# MCP_IO_expander.net
KiCad netlist of a schematic drawn in Altium Designer
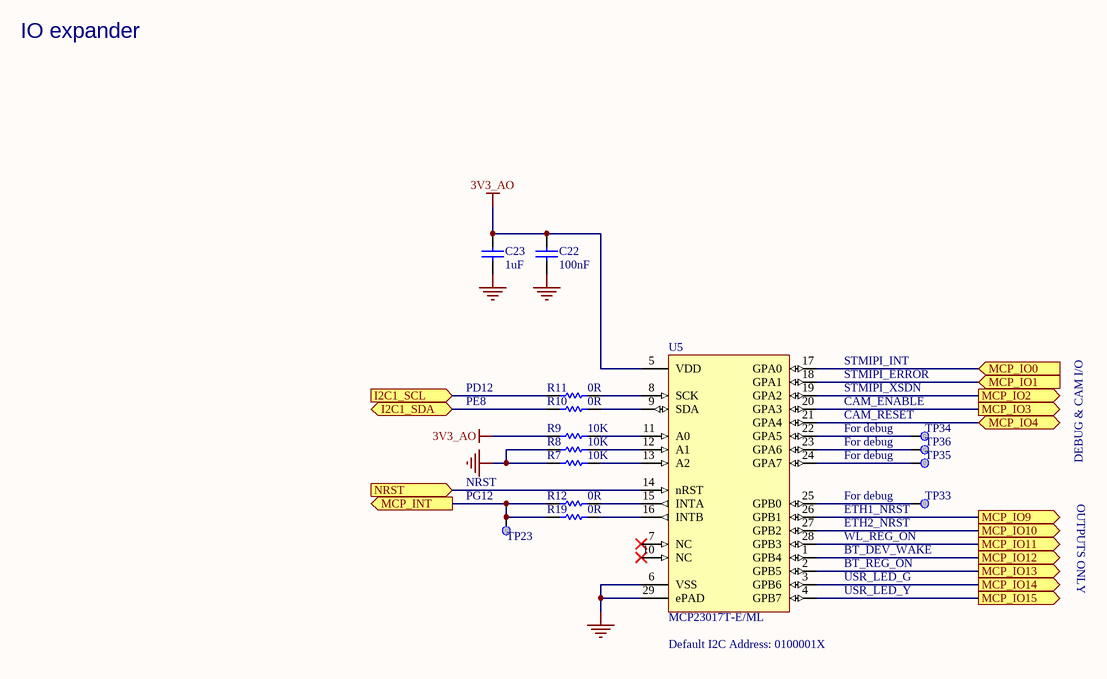
[diagram p0: MCP_IO_expander.SchDoc]

(export (version "E")
  (design (tool "Eeschema 10.0.6"))
  (components
    (comp (ref "C22")
      (value "100nF")
      (footprint "C0402")
      (description "Capacitor, MLCC, 100nF, 16V, X7R, +/-10%, 0402, T=0.5mm")
      (fields (field (name "INTERNAL_PART_NUMBER") "MCD-00006") (field (name "MANUFACTURER") "YAGEO"))
      (libsource (lib "MCD_PARTS_database") (part "Capacitor"))
    )
    (comp (ref "C23")
      (value "1uF")
      (footprint "C0201_MURATA_GRM033_H0P3")
      (description "Capacitor, MLCC, 1uF, 6.3V, X5R, +/-20%, 0201, T=0,3mm")
      (fields (field (name "INTERNAL_PART_NUMBER") "MCD-02377") (field (name "MANUFACTURER") "MURATA"))
      (libsource (lib "MCD_PARTS_database") (part "Capacitor"))
    )
    (comp (ref "R7")
      (value "10K")
      (footprint "R0402")
      (description "Resistor, 10K, 0402, +/-1%, 1/16W")
      (fields (field (name "INTERNAL_PART_NUMBER") "MCD-00053") (field (name "BMS_PART_NUMBER") "9131590"))
      (libsource (lib "MCD_PARTS_database") (part "Resistor"))
    )
    (comp (ref "R8")
      (value "10K")
      (footprint "R0402")
      (description "Resistor, 10K, 0402, +/-1%, 1/16W")
      (fields (field (name "INTERNAL_PART_NUMBER") "MCD-00053") (field (name "BMS_PART_NUMBER") "9131590"))
      (libsource (lib "MCD_PARTS_database") (part "Resistor"))
    )
    (comp (ref "R9")
      (value "10K")
      (footprint "R0402")
      (description "Resistor, 10K, 0402, +/-1%, 1/16W")
      (fields (field (name "INTERNAL_PART_NUMBER") "MCD-00053") (field (name "BMS_PART_NUMBER") "9131590"))
      (libsource (lib "MCD_PARTS_database") (part "Resistor"))
    )
    (comp (ref "R10")
      (value "0R")
      (footprint "R0402")
      (description "Resistor, 0R, 0402, +/-5%, 1/16W")
      (fields (field (name "INTERNAL_PART_NUMBER") "MCD-00052") (field (name "MANUFACTURER") "YAGEO"))
      (libsource (lib "MCD_PARTS_database") (part "Resistor"))
    )
    (comp (ref "R11")
      (value "0R")
      (footprint "R0402")
      (description "Resistor, 0R, 0402, +/-5%, 1/16W")
      (fields (field (name "INTERNAL_PART_NUMBER") "MCD-00052") (field (name "MANUFACTURER") "YAGEO"))
      (libsource (lib "MCD_PARTS_database") (part "Resistor"))
    )
    (comp (ref "R12")
      (value "0R")
      (footprint "R0402")
      (description "Resistor, 0R, 0402, +/-5%, 1/16W")
      (fields (field (name "INTERNAL_PART_NUMBER") "MCD-00052") (field (name "MANUFACTURER") "YAGEO"))
      (libsource (lib "MCD_PARTS_database") (part "Resistor"))
    )
    (comp (ref "R19")
      (value "0R")
      (footprint "R0402")
      (description "Resistor, 0R, 0402, +/-5%, 1/16W")
      (fields (field (name "INTERNAL_PART_NUMBER") "MCD-00052") (field (name "MANUFACTURER") "YAGEO"))
      (libsource (lib "MCD_PARTS_database") (part "Resistor"))
    )
    (comp (ref "TP23")
      (value "Test Point")
      (footprint "TP_SMD_1MM")
      (description "Test Point 1mm")
      (fields (field (name "INTERNAL_PART_NUMBER") "MCD-00074"))
      (libsource (lib "") (part "Test Point_1"))
    )
    (comp (ref "TP33")
      (value "Test Point")
      (footprint "TP_SMD_1MM")
      (description "Test Point 1mm")
      (fields (field (name "INTERNAL_PART_NUMBER") "MCD-00074"))
      (libsource (lib "MCD_PARTS_database") (part "Test Point"))
    )
    (comp (ref "TP34")
      (value "Test Point")
      (footprint "TP_SMD_1MM")
      (description "Test Point 1mm")
      (fields (field (name "INTERNAL_PART_NUMBER") "MCD-00074"))
      (libsource (lib "MCD_PARTS_database") (part "Test Point"))
    )
    (comp (ref "TP35")
      (value "Test Point")
      (footprint "TP_SMD_1MM")
      (description "Test Point 1mm")
      (fields (field (name "INTERNAL_PART_NUMBER") "MCD-00074"))
      (libsource (lib "MCD_PARTS_database") (part "Test Point"))
    )
    (comp (ref "TP36")
      (value "Test Point")
      (footprint "TP_SMD_1MM")
      (description "Test Point 1mm")
      (fields (field (name "INTERNAL_PART_NUMBER") "MCD-00074"))
      (libsource (lib "MCD_PARTS_database") (part "Test Point"))
    )
    (comp (ref "U5")
      (value "MCP23017T-E/ML")
      (footprint "ICC_QFN28-EPAD_6X6_P065")
      (description "16-bit port expander with I2C control")
      (fields (field (name "INTERNAL_PART_NUMBER") "MCD-02210") (field (name "MANUFACTURER") "MICROCHIP"))
      (libsource (lib "MCD_PARTS_database") (part "MCP23017"))
    )
  )
  (nets
    (net (code "1") (name "/I2C1_SCL") (class "Default")
      (node (ref "R11") (pin "1") (pinfunction "1_1") (pintype "passive"))
    )
    (net (code "2") (name "/I2C1_SDA") (class "Default")
      (node (ref "R10") (pin "1") (pinfunction "1_1") (pintype "passive"))
    )
    (net (code "3") (name "/MCP_INT") (class "Default")
      (node (ref "R12") (pin "1") (pinfunction "1_1") (pintype "passive"))
      (node (ref "R19") (pin "1") (pinfunction "1_1") (pintype "passive"))
      (node (ref "TP23") (pin "1") (pinfunction "1_1") (pintype "passive"))
    )
    (net (code "4") (name "/MCP_IO0") (class "Default")
      (node (ref "U5") (pin "17") (pinfunction "GPA0_17") (pintype "bidirectional"))
    )
    (net (code "5") (name "/MCP_IO1") (class "Default")
      (node (ref "U5") (pin "18") (pinfunction "GPA1_18") (pintype "bidirectional"))
    )
    (net (code "6") (name "/MCP_IO2") (class "Default")
      (node (ref "U5") (pin "19") (pinfunction "GPA2_19") (pintype "bidirectional"))
    )
    (net (code "7") (name "/MCP_IO3") (class "Default")
      (node (ref "U5") (pin "20") (pinfunction "GPA3_20") (pintype "bidirectional"))
    )
    (net (code "8") (name "/MCP_IO4") (class "Default")
      (node (ref "U5") (pin "21") (pinfunction "GPA4_21") (pintype "bidirectional"))
    )
    (net (code "9") (name "/MCP_IO9") (class "Default")
      (node (ref "U5") (pin "26") (pinfunction "GPB1_26") (pintype "bidirectional"))
    )
    (net (code "10") (name "/MCP_IO10") (class "Default")
      (node (ref "U5") (pin "27") (pinfunction "GPB2_27") (pintype "bidirectional"))
    )
    (net (code "11") (name "/MCP_IO11") (class "Default")
      (node (ref "U5") (pin "28") (pinfunction "GPB3_28") (pintype "bidirectional"))
    )
    (net (code "12") (name "/MCP_IO12") (class "Default")
      (node (ref "U5") (pin "1") (pinfunction "GPB4_1") (pintype "bidirectional"))
    )
    (net (code "13") (name "/MCP_IO13") (class "Default")
      (node (ref "U5") (pin "2") (pinfunction "GPB5_2") (pintype "bidirectional"))
    )
    (net (code "14") (name "/MCP_IO14") (class "Default")
      (node (ref "U5") (pin "3") (pinfunction "GPB6_3") (pintype "bidirectional"))
    )
    (net (code "15") (name "/MCP_IO15") (class "Default")
      (node (ref "U5") (pin "4") (pinfunction "GPB7_4") (pintype "bidirectional"))
    )
    (net (code "16") (name "/NRST") (class "Default")
      (node (ref "U5") (pin "14") (pinfunction "nRST_14") (pintype "input"))
    )
    (net (code "17") (name "3V3_AO") (class "Default")
      (node (ref "C22") (pin "2") (pinfunction "2_2") (pintype "passive"))
      (node (ref "C23") (pin "2") (pinfunction "2_2") (pintype "passive"))
      (node (ref "R9") (pin "1") (pinfunction "1_1") (pintype "passive"))
      (node (ref "U5") (pin "5") (pinfunction "VDD_5") (pintype "power_in"))
    )
    (net (code "18") (name "GND") (class "Default")
      (node (ref "C22") (pin "1") (pinfunction "1_1") (pintype "passive"))
      (node (ref "C23") (pin "1") (pinfunction "1_1") (pintype "passive"))
      (node (ref "R7") (pin "1") (pinfunction "1_1") (pintype "passive"))
      (node (ref "R8") (pin "1") (pinfunction "1_1") (pintype "passive"))
      (node (ref "U5") (pin "29") (pinfunction "ePAD_29") (pintype "power_in"))
      (node (ref "U5") (pin "6") (pinfunction "VSS_6") (pintype "power_in"))
    )
    (net (code "19") (name "Net-(U5-A0)") (class "Default")
      (node (ref "R9") (pin "2") (pinfunction "2_2") (pintype "passive"))
      (node (ref "U5") (pin "11") (pinfunction "A0_11") (pintype "input"))
    )
    (net (code "20") (name "Net-(U5-A1)") (class "Default")
      (node (ref "R8") (pin "2") (pinfunction "2_2") (pintype "passive"))
      (node (ref "U5") (pin "12") (pinfunction "A1_12") (pintype "input"))
    )
    (net (code "21") (name "Net-(U5-A2)") (class "Default")
      (node (ref "R7") (pin "2") (pinfunction "2_2") (pintype "passive"))
      (node (ref "U5") (pin "13") (pinfunction "A2_13") (pintype "input"))
    )
    (net (code "22") (name "Net-(U5-GPA5)") (class "Default")
      (node (ref "TP34") (pin "1") (pinfunction "1_1") (pintype "passive"))
      (node (ref "U5") (pin "22") (pinfunction "GPA5_22") (pintype "bidirectional"))
    )
    (net (code "23") (name "Net-(U5-GPA6)") (class "Default")
      (node (ref "TP36") (pin "1") (pinfunction "1_1") (pintype "passive"))
      (node (ref "U5") (pin "23") (pinfunction "GPA6_23") (pintype "bidirectional"))
    )
    (net (code "24") (name "Net-(U5-GPA7)") (class "Default")
      (node (ref "TP35") (pin "1") (pinfunction "1_1") (pintype "passive"))
      (node (ref "U5") (pin "24") (pinfunction "GPA7_24") (pintype "bidirectional"))
    )
    (net (code "25") (name "Net-(U5-GPB0)") (class "Default")
      (node (ref "TP33") (pin "1") (pinfunction "1_1") (pintype "passive"))
      (node (ref "U5") (pin "25") (pinfunction "GPB0_25") (pintype "bidirectional"))
    )
    (net (code "26") (name "Net-(U5-INTA)") (class "Default")
      (node (ref "R12") (pin "2") (pinfunction "2_2") (pintype "passive"))
      (node (ref "U5") (pin "15") (pinfunction "INTA_15") (pintype "output"))
    )
    (net (code "27") (name "Net-(U5-INTB)") (class "Default")
      (node (ref "R19") (pin "2") (pinfunction "2_2") (pintype "passive"))
      (node (ref "U5") (pin "16") (pinfunction "INTB_16") (pintype "output"))
    )
    (net (code "28") (name "Net-(U5-SCK)") (class "Default")
      (node (ref "R11") (pin "2") (pinfunction "2_2") (pintype "passive"))
      (node (ref "U5") (pin "8") (pinfunction "SCK_8") (pintype "input"))
    )
    (net (code "29") (name "Net-(U5-SDA)") (class "Default")
      (node (ref "R10") (pin "2") (pinfunction "2_2") (pintype "passive"))
      (node (ref "U5") (pin "9") (pinfunction "SDA_9") (pintype "bidirectional"))
    )
    (net (code "30") (name "unconnected-(U5-NC-Pad7)") (class "Default")
      (node (ref "U5") (pin "7") (pinfunction "NC_7") (pintype "input+no_connect"))
    )
    (net (code "31") (name "unconnected-(U5-NC-Pad10)") (class "Default")
      (node (ref "U5") (pin "10") (pinfunction "NC_10") (pintype "input+no_connect"))
    )
  )
)
